# DC_Converter.net
KiCad netlist of a schematic drawn in Altium Designer
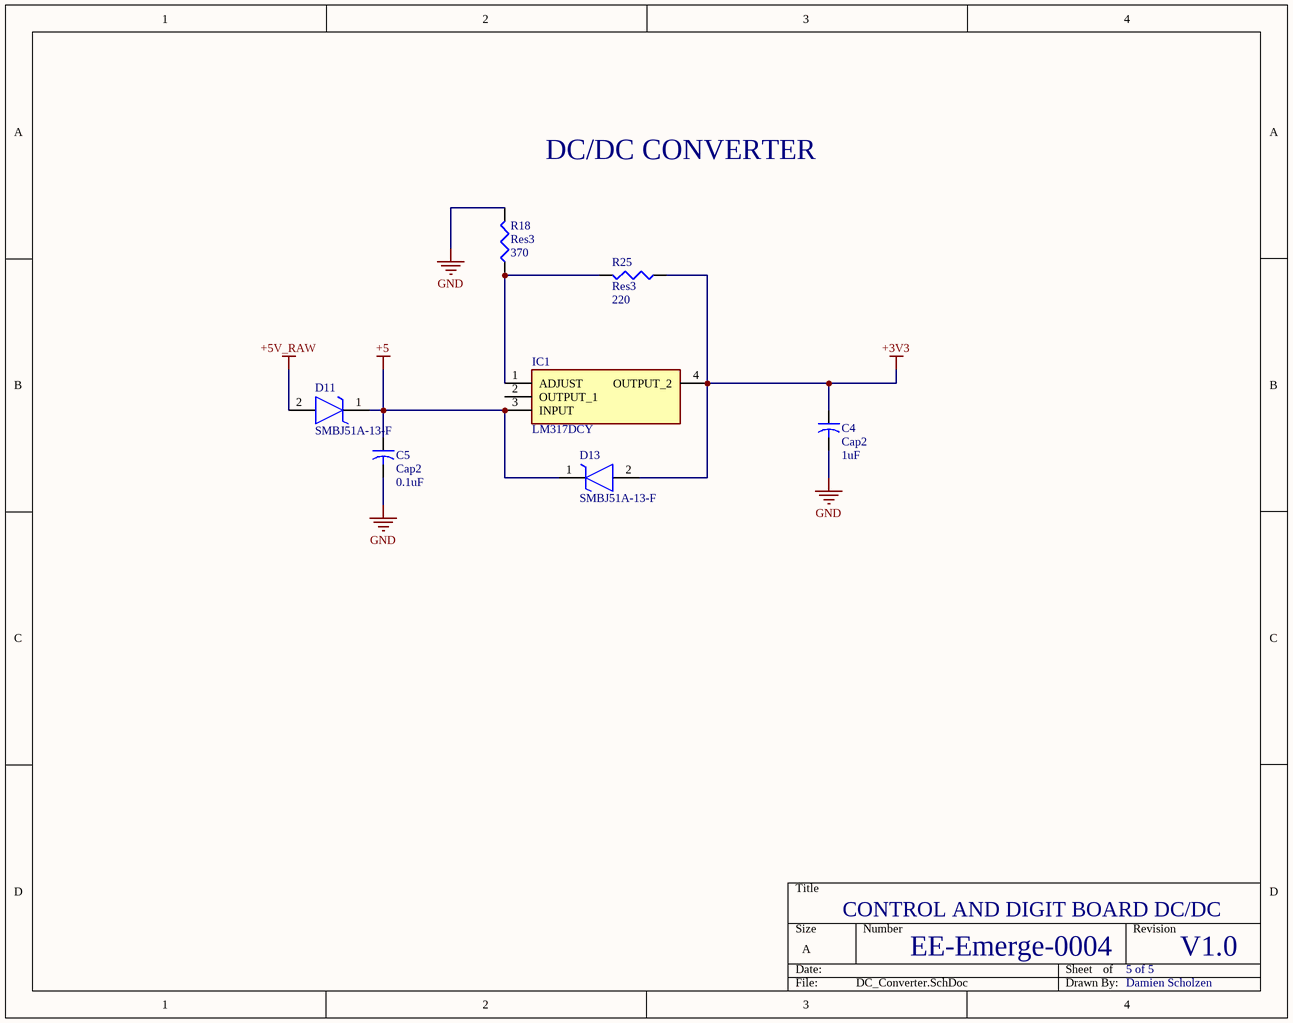
[diagram p0: DC_Converter.SchDoc]

(export (version "E")
  (design (tool "Eeschema 10.0.6"))
  (components
    (comp (ref "C4")
      (value "Cap2")
      (footprint "C0805")
      (description "Capacitor")
      (fields (field (name "ALTIUM_VALUE") "1uF") (field (name "PUBLISHER") "Altium Limited"))
      (libsource (lib "EE_Emerge_SkillsProject (1)") (part "Cap2_1"))
    )
    (comp (ref "C5")
      (value "Cap2")
      (footprint "C0805")
      (description "Capacitor")
      (fields (field (name "ALTIUM_VALUE") "0.1uF") (field (name "PUBLISHER") "Altium Limited"))
      (libsource (lib "EE_Emerge_SkillsProject (1)") (part "Cap2_2"))
    )
    (comp (ref "D11")
      (value "SMBJ51A-13-F")
      (footprint "SamacSys:DIOM5336X250N")
      (description "TVS Diode (Uni-directional)")
      (fields (field (name "MOUSER PART NUMBER") "621-SMBJ51A-13-F"))
      (libsource (lib "*") (part "SMBJ51A-13-F"))
    )
    (comp (ref "D13")
      (value "SMBJ51A-13-F")
      (footprint "SamacSys:DIOM5336X250N")
      (description "TVS Diode (Uni-directional)")
      (fields (field (name "MOUSER PART NUMBER") "621-SMBJ51A-13-F"))
      (libsource (lib "*") (part "SMBJ51A-13-F"))
    )
    (comp (ref "IC1")
      (value "LM317DCY")
      (footprint "SamacSys:SOT230P700X180-4N")
      (description "Integrated Circuit")
      (fields (field (name "MOUSER PART NUMBER") "595-LM317DCY"))
      (libsource (lib "*") (part "LM317DCY"))
    )
    (comp (ref "R18")
      (value "Res3")
      (footprint "J1-0603")
      (description "Resistor")
      (fields (field (name "ALTIUM_VALUE") "370") (field (name "PUBLISHER") "Altium Limited"))
      (libsource (lib "Miscellaneous Devices") (part "Res3"))
    )
    (comp (ref "R25")
      (value "Res3")
      (footprint "J1-0603")
      (description "Resistor")
      (fields (field (name "ALTIUM_VALUE") "220") (field (name "PUBLISHER") "Altium Limited"))
      (libsource (lib "Miscellaneous Devices") (part "Res3"))
    )
  )
  (nets
    (net (code "1") (name "+3V3") (class "Default")
      (node (ref "C4") (pin "1") (pinfunction "1_1") (pintype "passive"))
      (node (ref "D13") (pin "2") (pinfunction "A_2") (pintype "passive"))
      (node (ref "IC1") (pin "4") (pinfunction "OUTPUT_2_4") (pintype "passive"))
      (node (ref "R25") (pin "1") (pinfunction "1_1") (pintype "passive"))
    )
    (net (code "2") (name "+5") (class "Default")
      (node (ref "C5") (pin "1") (pinfunction "1_1") (pintype "passive"))
      (node (ref "D11") (pin "1") (pinfunction "K_1") (pintype "passive"))
      (node (ref "D13") (pin "1") (pinfunction "K_1") (pintype "passive"))
      (node (ref "IC1") (pin "3") (pinfunction "INPUT_3") (pintype "passive"))
    )
    (net (code "3") (name "+5V_RAW") (class "Default")
      (node (ref "D11") (pin "2") (pinfunction "A_2") (pintype "passive"))
    )
    (net (code "4") (name "GND") (class "Default")
      (node (ref "C4") (pin "2") (pinfunction "2_2") (pintype "passive"))
      (node (ref "C5") (pin "2") (pinfunction "2_2") (pintype "passive"))
      (node (ref "R18") (pin "2") (pinfunction "2_2") (pintype "passive"))
    )
    (net (code "5") (name "Net-(IC1-ADJUST)") (class "Default")
      (node (ref "IC1") (pin "1") (pinfunction "ADJUST_1") (pintype "passive"))
      (node (ref "R18") (pin "1") (pinfunction "1_1") (pintype "passive"))
      (node (ref "R25") (pin "2") (pinfunction "2_2") (pintype "passive"))
    )
    (net (code "6") (name "unconnected-(IC1-OUTPUT_1-Pad2)") (class "Default")
      (node (ref "IC1") (pin "2") (pinfunction "OUTPUT_1_2") (pintype "passive"))
    )
  )
)
